# rcstick-f.net
KiCad netlist of a schematic drawn in EAGLE
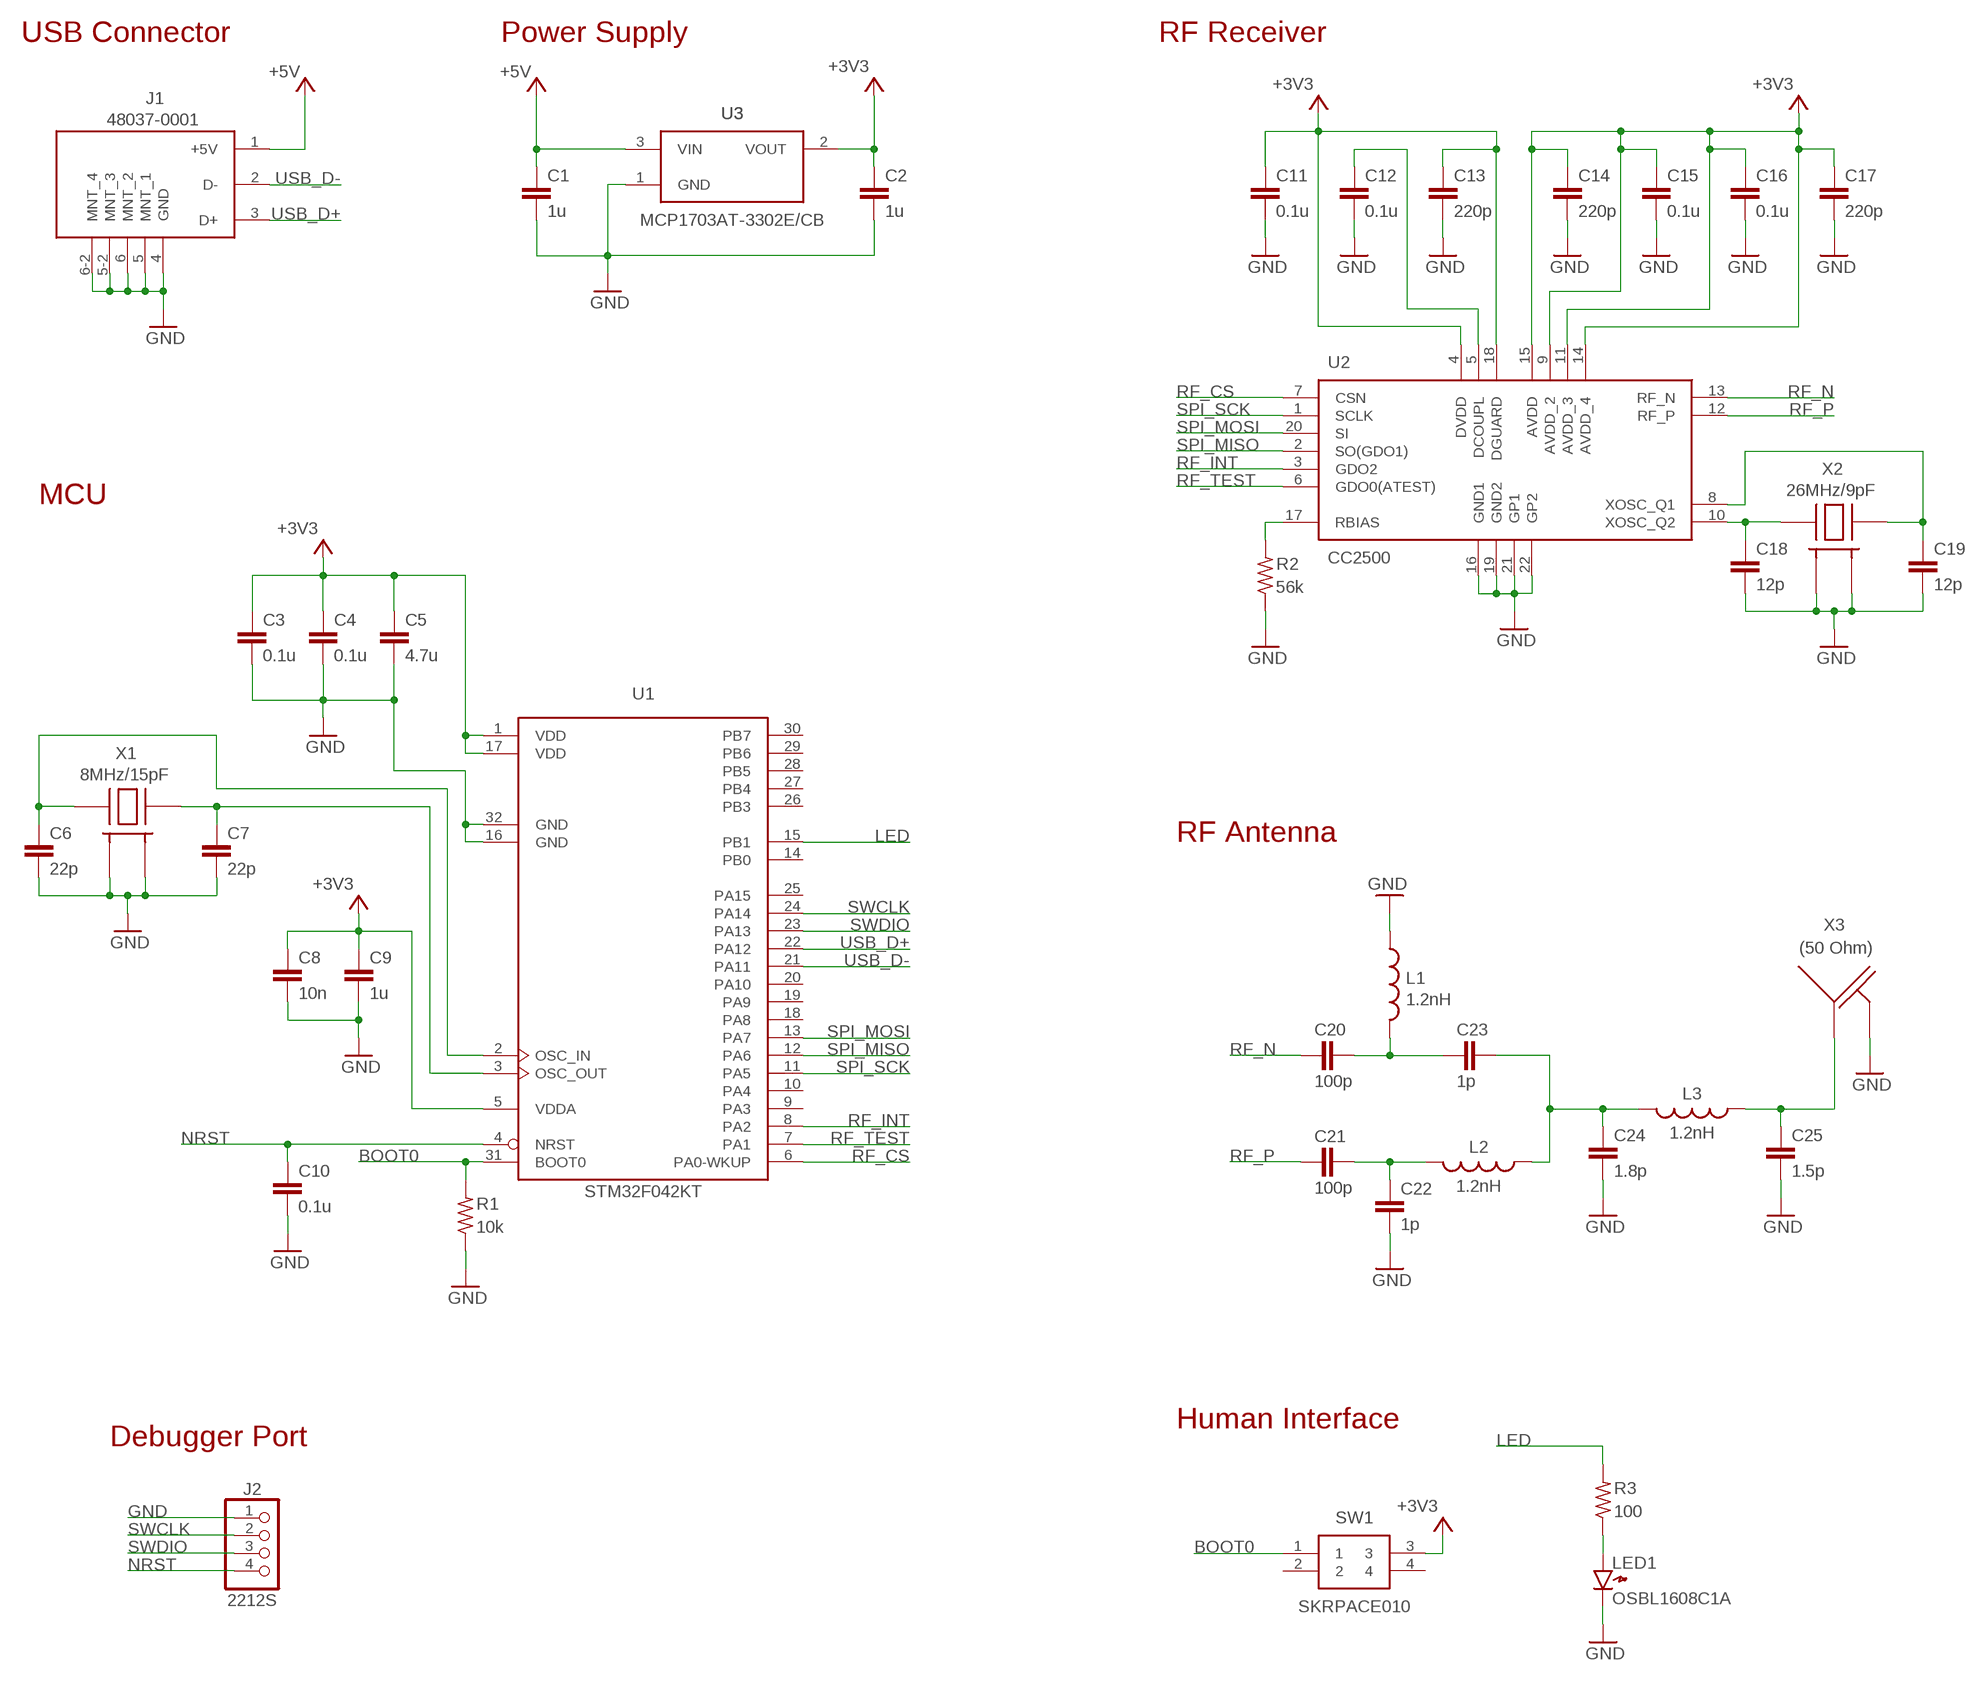
[diagram p0: schematic, sheet 1]

(export (version "E")
  (design (tool "Eeschema 10.0.6"))
  (components
    (comp (ref "C1")
      (value "1u")
      (footprint "eagle-import:RCL_C0402_HS")
      (libsource (lib "eagle-import") (part "RCL_C-EUC0402-HS"))
    )
    (comp (ref "C2")
      (value "1u")
      (footprint "eagle-import:RCL_C0402_HS")
      (libsource (lib "eagle-import") (part "RCL_C-EUC0402-HS"))
    )
    (comp (ref "C3")
      (value "0.1u")
      (footprint "eagle-import:RCL_C0402_HS")
      (libsource (lib "eagle-import") (part "RCL_C-EUC0402-HS"))
    )
    (comp (ref "C4")
      (value "0.1u")
      (footprint "eagle-import:RCL_C0402_HS")
      (libsource (lib "eagle-import") (part "RCL_C-EUC0402-HS"))
    )
    (comp (ref "C5")
      (value "4.7u")
      (footprint "eagle-import:RCL_C0402_HS")
      (libsource (lib "eagle-import") (part "RCL_C-EUC0402-HS"))
    )
    (comp (ref "C6")
      (value "22p")
      (footprint "eagle-import:RCL_C0402_HS")
      (libsource (lib "eagle-import") (part "RCL_C-EUC0402-HS"))
    )
    (comp (ref "C7")
      (value "22p")
      (footprint "eagle-import:RCL_C0402_HS")
      (libsource (lib "eagle-import") (part "RCL_C-EUC0402-HS"))
    )
    (comp (ref "C8")
      (value "10n")
      (footprint "eagle-import:RCL_C0402_HS")
      (libsource (lib "eagle-import") (part "RCL_C-EUC0402-HS"))
    )
    (comp (ref "C9")
      (value "1u")
      (footprint "eagle-import:RCL_C0402_HS")
      (libsource (lib "eagle-import") (part "RCL_C-EUC0402-HS"))
    )
    (comp (ref "C10")
      (value "0.1u")
      (footprint "eagle-import:RCL_C0402_HS")
      (libsource (lib "eagle-import") (part "RCL_C-EUC0402-HS"))
    )
    (comp (ref "C11")
      (value "0.1u")
      (footprint "eagle-import:RCL_C0402_HS")
      (libsource (lib "eagle-import") (part "RCL_C-EUC0402-HS"))
    )
    (comp (ref "C12")
      (value "0.1u")
      (footprint "eagle-import:RCL_C0402_HS")
      (libsource (lib "eagle-import") (part "RCL_C-EUC0402-HS"))
    )
    (comp (ref "C13")
      (value "220p")
      (footprint "eagle-import:RCL_C0402_HS")
      (libsource (lib "eagle-import") (part "RCL_C-EUC0402-HS"))
    )
    (comp (ref "C14")
      (value "220p")
      (footprint "eagle-import:RCL_C0402_HS")
      (libsource (lib "eagle-import") (part "RCL_C-EUC0402-HS"))
    )
    (comp (ref "C15")
      (value "0.1u")
      (footprint "eagle-import:RCL_C0402_HS")
      (libsource (lib "eagle-import") (part "RCL_C-EUC0402-HS"))
    )
    (comp (ref "C16")
      (value "0.1u")
      (footprint "eagle-import:RCL_C0402_HS")
      (libsource (lib "eagle-import") (part "RCL_C-EUC0402-HS"))
    )
    (comp (ref "C17")
      (value "220p")
      (footprint "eagle-import:RCL_C0402_HS")
      (libsource (lib "eagle-import") (part "RCL_C-EUC0402-HS"))
    )
    (comp (ref "C18")
      (value "12p")
      (footprint "eagle-import:RCL_C0402_HS")
      (libsource (lib "eagle-import") (part "RCL_C-EUC0402-HS"))
    )
    (comp (ref "C19")
      (value "12p")
      (footprint "eagle-import:RCL_C0402_HS")
      (libsource (lib "eagle-import") (part "RCL_C-EUC0402-HS"))
    )
    (comp (ref "C20")
      (value "100p")
      (footprint "eagle-import:RCL_C0402_HS")
      (libsource (lib "eagle-import") (part "RCL_C-EUC0402-HS"))
    )
    (comp (ref "C21")
      (value "100p")
      (footprint "eagle-import:RCL_C0402_HS")
      (libsource (lib "eagle-import") (part "RCL_C-EUC0402-HS"))
    )
    (comp (ref "C22")
      (value "1p")
      (footprint "eagle-import:RCL_C0402_HS")
      (libsource (lib "eagle-import") (part "RCL_C-EUC0402-HS"))
    )
    (comp (ref "C23")
      (value "1p")
      (footprint "eagle-import:RCL_C0402_HS")
      (libsource (lib "eagle-import") (part "RCL_C-EUC0402-HS"))
    )
    (comp (ref "C24")
      (value "1.8p")
      (footprint "eagle-import:RCL_C0402_HS")
      (libsource (lib "eagle-import") (part "RCL_C-EUC0402-HS"))
    )
    (comp (ref "C25")
      (value "1.5p")
      (footprint "eagle-import:RCL_C0402_HS")
      (libsource (lib "eagle-import") (part "RCL_C-EUC0402-HS"))
    )
    (comp (ref "J1")
      (value "MOLEX_48037-0001")
      (footprint "eagle-import:MOLEX_48037-0001_1")
      (libsource (lib "eagle-import") (part "MOLEX_48037-0001"))
    )
    (comp (ref "J2")
      (value "2212S")
      (footprint "eagle-import:CONNECTOR_STD-1X4")
      (libsource (lib "eagle-import") (part "CONNECTOR_STD-PINHD-1X4"))
    )
    (comp (ref "L1")
      (value "1.2nH")
      (footprint "eagle-import:RCL_L0402_HS")
      (libsource (lib "eagle-import") (part "RCL_L-USL0402-HS"))
    )
    (comp (ref "L2")
      (value "1.2nH")
      (footprint "eagle-import:RCL_L0402_HS")
      (libsource (lib "eagle-import") (part "RCL_L-USL0402-HS"))
    )
    (comp (ref "L3")
      (value "1.2nH")
      (footprint "eagle-import:RCL_L0402_HS")
      (libsource (lib "eagle-import") (part "RCL_L-USL0402-HS"))
    )
    (comp (ref "LED1")
      (value "OSBL1608C1A")
      (footprint "eagle-import:LED1608")
      (libsource (lib "eagle-import") (part "LED1608"))
    )
    (comp (ref "R1")
      (value "10k")
      (footprint "eagle-import:RCL_R0402_HS")
      (libsource (lib "eagle-import") (part "RCL_R-US_R0402-HS"))
    )
    (comp (ref "R2")
      (value "56k")
      (footprint "eagle-import:RCL_R0402_HS")
      (libsource (lib "eagle-import") (part "RCL_R-US_R0402-HS"))
    )
    (comp (ref "R3")
      (value "100")
      (footprint "eagle-import:RCL_R0402_HS")
      (libsource (lib "eagle-import") (part "RCL_R-US_R0402-HS"))
    )
    (comp (ref "SW1")
      (value "SKRPACE010")
      (footprint "eagle-import:SMT(4.2X3.2)")
      (libsource (lib "eagle-import") (part "SKRPACE010"))
    )
    (comp (ref "U1")
      (value "STM32F042KT")
      (footprint "eagle-import:LQFP32-M")
      (libsource (lib "eagle-import") (part "STM32F042KT"))
    )
    (comp (ref "U2")
      (value "CC2500")
      (footprint "eagle-import:CC2500-RTY1_CC2500-HS")
      (libsource (lib "eagle-import") (part "CC2500-HS"))
    )
    (comp (ref "U3")
      (value "MCP1703AT-3302E/CB")
      (footprint "eagle-import:SOT23")
      (libsource (lib "eagle-import") (part "LDO-REGULATOR"))
    )
    (comp (ref "X1")
      (value "8MHz/15pF")
      (footprint "eagle-import:CRYSTAL3225-HS")
      (libsource (lib "eagle-import") (part "CRYSTAL3225HS"))
    )
    (comp (ref "X2")
      (value "26MHz/9pF")
      (footprint "eagle-import:CRYSTAL3225-HS")
      (libsource (lib "eagle-import") (part "CRYSTAL3225HS"))
    )
    (comp (ref "X3")
      (value "(50 Ohm)")
      (footprint "eagle-import:2.4GHZ-INVERTED-F-LARGE-FLIP")
      (libsource (lib "eagle-import") (part "2.4GHZ-INVERED-FLARGE-FLIP"))
    )
  )
  (nets
    (net (code "1") (name "+3V3") (class "Default")
      (node (ref "C11") (pin "1") (pinfunction "1_1") (pintype "passive"))
      (node (ref "C13") (pin "1") (pinfunction "1_1") (pintype "passive"))
      (node (ref "C14") (pin "1") (pinfunction "1_1") (pintype "passive"))
      (node (ref "C15") (pin "1") (pinfunction "1_1") (pintype "passive"))
      (node (ref "C16") (pin "1") (pinfunction "1_1") (pintype "passive"))
      (node (ref "C17") (pin "1") (pinfunction "1_1") (pintype "passive"))
      (node (ref "C2") (pin "1") (pinfunction "1_1") (pintype "passive"))
      (node (ref "C3") (pin "1") (pinfunction "1_1") (pintype "passive"))
      (node (ref "C4") (pin "1") (pinfunction "1_1") (pintype "passive"))
      (node (ref "C5") (pin "1") (pinfunction "1_1") (pintype "passive"))
      (node (ref "C8") (pin "1") (pinfunction "1_1") (pintype "passive"))
      (node (ref "C9") (pin "1") (pinfunction "1_1") (pintype "passive"))
      (node (ref "SW1") (pin "3") (pinfunction "3_3") (pintype "bidirectional"))
      (node (ref "U1") (pin "1") (pinfunction "VDD_1") (pintype "power_in"))
      (node (ref "U1") (pin "17") (pinfunction "VDD_17") (pintype "power_in"))
      (node (ref "U1") (pin "5") (pinfunction "VDDA_5") (pintype "power_in"))
      (node (ref "U2") (pin "11") (pinfunction "AVDD_3_11") (pintype "bidirectional"))
      (node (ref "U2") (pin "14") (pinfunction "AVDD_4_14") (pintype "bidirectional"))
      (node (ref "U2") (pin "15") (pinfunction "AVDD_15") (pintype "bidirectional"))
      (node (ref "U2") (pin "18") (pinfunction "DGUARD_18") (pintype "bidirectional"))
      (node (ref "U2") (pin "4") (pinfunction "DVDD_4") (pintype "bidirectional"))
      (node (ref "U2") (pin "9") (pinfunction "AVDD_2_9") (pintype "bidirectional"))
      (node (ref "U3") (pin "2") (pinfunction "VOUT_2") (pintype "bidirectional"))
    )
    (net (code "2") (name "+5V") (class "Default")
      (node (ref "C1") (pin "1") (pinfunction "1_1") (pintype "passive"))
      (node (ref "J1") (pin "1") (pinfunction "+5V_1") (pintype "bidirectional"))
      (node (ref "U3") (pin "3") (pinfunction "VIN_3") (pintype "bidirectional"))
    )
    (net (code "3") (name "/BOOT0") (class "Default")
      (node (ref "R1") (pin "2") (pinfunction "2_2") (pintype "passive"))
      (node (ref "SW1") (pin "1") (pinfunction "1_1") (pintype "bidirectional"))
      (node (ref "U1") (pin "31") (pinfunction "BOOT0_31") (pintype "input"))
    )
    (net (code "4") (name "/LED") (class "Default")
      (node (ref "R3") (pin "2") (pinfunction "2_2") (pintype "passive"))
      (node (ref "U1") (pin "15") (pinfunction "PB1_15") (pintype "bidirectional"))
    )
    (net (code "5") (name "/NRST") (class "Default")
      (node (ref "C10") (pin "1") (pinfunction "1_1") (pintype "passive"))
      (node (ref "J2") (pin "4") (pinfunction "4_4") (pintype "passive"))
      (node (ref "U1") (pin "4") (pinfunction "NRST_4") (pintype "bidirectional"))
    )
    (net (code "6") (name "/RF_CS") (class "Default")
      (node (ref "U1") (pin "6") (pinfunction "PA0-WKUP_6") (pintype "bidirectional"))
      (node (ref "U2") (pin "7") (pinfunction "CSN_7") (pintype "bidirectional"))
    )
    (net (code "7") (name "/RF_INT") (class "Default")
      (node (ref "U1") (pin "8") (pinfunction "PA2_8") (pintype "bidirectional"))
      (node (ref "U2") (pin "3") (pinfunction "GDO2_3") (pintype "bidirectional"))
    )
    (net (code "8") (name "/RF_N") (class "Default")
      (node (ref "C20") (pin "1") (pinfunction "1_1") (pintype "passive"))
      (node (ref "U2") (pin "13") (pinfunction "RF_N_13") (pintype "bidirectional"))
    )
    (net (code "9") (name "/RF_P") (class "Default")
      (node (ref "C21") (pin "1") (pinfunction "1_1") (pintype "passive"))
      (node (ref "U2") (pin "12") (pinfunction "RF_P_12") (pintype "bidirectional"))
    )
    (net (code "10") (name "/RF_TEST") (class "Default")
      (node (ref "U1") (pin "7") (pinfunction "PA1_7") (pintype "bidirectional"))
      (node (ref "U2") (pin "6") (pinfunction "GDO0(ATEST)_6") (pintype "bidirectional"))
    )
    (net (code "11") (name "/SPI_MISO") (class "Default")
      (node (ref "U1") (pin "12") (pinfunction "PA6_12") (pintype "bidirectional"))
      (node (ref "U2") (pin "2") (pinfunction "SO(GDO1)_2") (pintype "bidirectional"))
    )
    (net (code "12") (name "/SPI_MOSI") (class "Default")
      (node (ref "U1") (pin "13") (pinfunction "PA7_13") (pintype "bidirectional"))
      (node (ref "U2") (pin "20") (pinfunction "SI_20") (pintype "bidirectional"))
    )
    (net (code "13") (name "/SPI_SCK") (class "Default")
      (node (ref "U1") (pin "11") (pinfunction "PA5_11") (pintype "bidirectional"))
      (node (ref "U2") (pin "1") (pinfunction "SCLK_1") (pintype "bidirectional"))
    )
    (net (code "14") (name "/SWCLK") (class "Default")
      (node (ref "J2") (pin "2") (pinfunction "2_2") (pintype "passive"))
      (node (ref "U1") (pin "24") (pinfunction "PA14_24") (pintype "bidirectional"))
    )
    (net (code "15") (name "/SWDIO") (class "Default")
      (node (ref "J2") (pin "3") (pinfunction "3_3") (pintype "passive"))
      (node (ref "U1") (pin "23") (pinfunction "PA13_23") (pintype "bidirectional"))
    )
    (net (code "16") (name "/USB_D+") (class "Default")
      (node (ref "J1") (pin "3") (pinfunction "D+_3") (pintype "bidirectional"))
      (node (ref "U1") (pin "22") (pinfunction "PA12_22") (pintype "bidirectional"))
    )
    (net (code "17") (name "/USB_D-") (class "Default")
      (node (ref "J1") (pin "2") (pinfunction "D-_2") (pintype "bidirectional"))
      (node (ref "U1") (pin "21") (pinfunction "PA11_21") (pintype "bidirectional"))
    )
    (net (code "18") (name "GND") (class "Default")
      (node (ref "C1") (pin "2") (pinfunction "2_2") (pintype "passive"))
      (node (ref "C10") (pin "2") (pinfunction "2_2") (pintype "passive"))
      (node (ref "C11") (pin "2") (pinfunction "2_2") (pintype "passive"))
      (node (ref "C12") (pin "2") (pinfunction "2_2") (pintype "passive"))
      (node (ref "C13") (pin "2") (pinfunction "2_2") (pintype "passive"))
      (node (ref "C14") (pin "2") (pinfunction "2_2") (pintype "passive"))
      (node (ref "C15") (pin "2") (pinfunction "2_2") (pintype "passive"))
      (node (ref "C16") (pin "2") (pinfunction "2_2") (pintype "passive"))
      (node (ref "C17") (pin "2") (pinfunction "2_2") (pintype "passive"))
      (node (ref "C18") (pin "2") (pinfunction "2_2") (pintype "passive"))
      (node (ref "C19") (pin "2") (pinfunction "2_2") (pintype "passive"))
      (node (ref "C2") (pin "2") (pinfunction "2_2") (pintype "passive"))
      (node (ref "C22") (pin "2") (pinfunction "2_2") (pintype "passive"))
      (node (ref "C24") (pin "2") (pinfunction "2_2") (pintype "passive"))
      (node (ref "C25") (pin "2") (pinfunction "2_2") (pintype "passive"))
      (node (ref "C3") (pin "2") (pinfunction "2_2") (pintype "passive"))
      (node (ref "C4") (pin "2") (pinfunction "2_2") (pintype "passive"))
      (node (ref "C5") (pin "2") (pinfunction "2_2") (pintype "passive"))
      (node (ref "C6") (pin "2") (pinfunction "2_2") (pintype "passive"))
      (node (ref "C7") (pin "2") (pinfunction "2_2") (pintype "passive"))
      (node (ref "C8") (pin "2") (pinfunction "2_2") (pintype "passive"))
      (node (ref "C9") (pin "2") (pinfunction "2_2") (pintype "passive"))
      (node (ref "J1") (pin "4") (pinfunction "GND_4") (pintype "bidirectional"))
      (node (ref "J1") (pin "5") (pinfunction "MNT_1_5") (pintype "bidirectional"))
      (node (ref "J1") (pin "5-2") (pinfunction "MNT_3_5-2") (pintype "bidirectional"))
      (node (ref "J1") (pin "6") (pinfunction "MNT_2_6") (pintype "bidirectional"))
      (node (ref "J1") (pin "6-2") (pinfunction "MNT_4_6-2") (pintype "bidirectional"))
      (node (ref "J2") (pin "1") (pinfunction "1_1") (pintype "passive"))
      (node (ref "L1") (pin "1") (pinfunction "1_1") (pintype "passive"))
      (node (ref "LED1") (pin "K") (pinfunction "K_K") (pintype "passive"))
      (node (ref "R1") (pin "1") (pinfunction "1_1") (pintype "passive"))
      (node (ref "R2") (pin "1") (pinfunction "1_1") (pintype "passive"))
      (node (ref "U1") (pin "16") (pinfunction "GND_16") (pintype "power_in"))
      (node (ref "U1") (pin "32") (pinfunction "GND_32") (pintype "power_in"))
      (node (ref "U2") (pin "16") (pinfunction "GND1_16") (pintype "bidirectional"))
      (node (ref "U2") (pin "19") (pinfunction "GND2_19") (pintype "bidirectional"))
      (node (ref "U2") (pin "21") (pinfunction "GP1_21") (pintype "bidirectional"))
      (node (ref "U2") (pin "22") (pinfunction "GP2_22") (pintype "bidirectional"))
      (node (ref "U3") (pin "1") (pinfunction "GND_1") (pintype "bidirectional"))
      (node (ref "X1") (pin "2") (pinfunction "GND_1_2") (pintype "bidirectional"))
      (node (ref "X1") (pin "4") (pinfunction "GND_2_4") (pintype "bidirectional"))
      (node (ref "X2") (pin "2") (pinfunction "GND_1_2") (pintype "bidirectional"))
      (node (ref "X2") (pin "4") (pinfunction "GND_2_4") (pintype "bidirectional"))
      (node (ref "X3") (pin "2") (pinfunction "GND_2") (pintype "bidirectional"))
    )
    (net (code "19") (name "Net-(C20-Pad2)") (class "Default")
      (node (ref "C20") (pin "2") (pinfunction "2_2") (pintype "passive"))
      (node (ref "C23") (pin "1") (pinfunction "1_1") (pintype "passive"))
      (node (ref "L1") (pin "2") (pinfunction "2_2") (pintype "passive"))
    )
    (net (code "20") (name "Net-(C21-Pad2)") (class "Default")
      (node (ref "C21") (pin "2") (pinfunction "2_2") (pintype "passive"))
      (node (ref "C22") (pin "1") (pinfunction "1_1") (pintype "passive"))
      (node (ref "L2") (pin "2") (pinfunction "2_2") (pintype "passive"))
    )
    (net (code "21") (name "Net-(C23-Pad2)") (class "Default")
      (node (ref "C23") (pin "2") (pinfunction "2_2") (pintype "passive"))
      (node (ref "C24") (pin "1") (pinfunction "1_1") (pintype "passive"))
      (node (ref "L2") (pin "1") (pinfunction "1_1") (pintype "passive"))
      (node (ref "L3") (pin "2") (pinfunction "2_2") (pintype "passive"))
    )
    (net (code "22") (name "Net-(LED1-PadA)") (class "Default")
      (node (ref "LED1") (pin "A") (pinfunction "A_A") (pintype "passive"))
      (node (ref "R3") (pin "1") (pinfunction "1_1") (pintype "passive"))
    )
    (net (code "23") (name "Net-(U1-OSC_IN)") (class "Default")
      (node (ref "C6") (pin "1") (pinfunction "1_1") (pintype "passive"))
      (node (ref "U1") (pin "2") (pinfunction "OSC_IN_2") (pintype "bidirectional"))
      (node (ref "X1") (pin "1") (pinfunction "HOT_1_1") (pintype "bidirectional"))
    )
    (net (code "24") (name "Net-(U1-OSC_OUT)") (class "Default")
      (node (ref "C7") (pin "1") (pinfunction "1_1") (pintype "passive"))
      (node (ref "U1") (pin "3") (pinfunction "OSC_OUT_3") (pintype "bidirectional"))
      (node (ref "X1") (pin "3") (pinfunction "HOT_2_3") (pintype "bidirectional"))
    )
    (net (code "25") (name "Net-(U2-DCOUPL)") (class "Default")
      (node (ref "C12") (pin "1") (pinfunction "1_1") (pintype "passive"))
      (node (ref "U2") (pin "5") (pinfunction "DCOUPL_5") (pintype "bidirectional"))
    )
    (net (code "26") (name "Net-(U2-RBIAS)") (class "Default")
      (node (ref "R2") (pin "2") (pinfunction "2_2") (pintype "passive"))
      (node (ref "U2") (pin "17") (pinfunction "RBIAS_17") (pintype "bidirectional"))
    )
    (net (code "27") (name "Net-(U2-XOSC_Q1)") (class "Default")
      (node (ref "C19") (pin "1") (pinfunction "1_1") (pintype "passive"))
      (node (ref "U2") (pin "8") (pinfunction "XOSC_Q1_8") (pintype "bidirectional"))
      (node (ref "X2") (pin "3") (pinfunction "HOT_2_3") (pintype "bidirectional"))
    )
    (net (code "28") (name "Net-(U2-XOSC_Q2)") (class "Default")
      (node (ref "C18") (pin "1") (pinfunction "1_1") (pintype "passive"))
      (node (ref "U2") (pin "10") (pinfunction "XOSC_Q2_10") (pintype "bidirectional"))
      (node (ref "X2") (pin "1") (pinfunction "HOT_1_1") (pintype "bidirectional"))
    )
    (net (code "29") (name "Net-(X3-ANT)") (class "Default")
      (node (ref "C25") (pin "1") (pinfunction "1_1") (pintype "passive"))
      (node (ref "L3") (pin "1") (pinfunction "1_1") (pintype "passive"))
      (node (ref "X3") (pin "1") (pinfunction "ANT_1") (pintype "bidirectional"))
    )
    (net (code "30") (name "unconnected-(SW1-Pad2)") (class "Default")
      (node (ref "SW1") (pin "2") (pinfunction "2_2") (pintype "bidirectional"))
    )
    (net (code "31") (name "unconnected-(SW1-Pad4)") (class "Default")
      (node (ref "SW1") (pin "4") (pinfunction "4_4") (pintype "bidirectional"))
    )
    (net (code "32") (name "unconnected-(U1-PA3-Pad9)") (class "Default")
      (node (ref "U1") (pin "9") (pinfunction "PA3_9") (pintype "bidirectional"))
    )
    (net (code "33") (name "unconnected-(U1-PA4-Pad10)") (class "Default")
      (node (ref "U1") (pin "10") (pinfunction "PA4_10") (pintype "bidirectional"))
    )
    (net (code "34") (name "unconnected-(U1-PA8-Pad18)") (class "Default")
      (node (ref "U1") (pin "18") (pinfunction "PA8_18") (pintype "bidirectional"))
    )
    (net (code "35") (name "unconnected-(U1-PA9-Pad19)") (class "Default")
      (node (ref "U1") (pin "19") (pinfunction "PA9_19") (pintype "bidirectional"))
    )
    (net (code "36") (name "unconnected-(U1-PA10-Pad20)") (class "Default")
      (node (ref "U1") (pin "20") (pinfunction "PA10_20") (pintype "bidirectional"))
    )
    (net (code "37") (name "unconnected-(U1-PA15-Pad25)") (class "Default")
      (node (ref "U1") (pin "25") (pinfunction "PA15_25") (pintype "bidirectional"))
    )
    (net (code "38") (name "unconnected-(U1-PB0-Pad14)") (class "Default")
      (node (ref "U1") (pin "14") (pinfunction "PB0_14") (pintype "bidirectional"))
    )
    (net (code "39") (name "unconnected-(U1-PB3-Pad26)") (class "Default")
      (node (ref "U1") (pin "26") (pinfunction "PB3_26") (pintype "bidirectional"))
    )
    (net (code "40") (name "unconnected-(U1-PB4-Pad27)") (class "Default")
      (node (ref "U1") (pin "27") (pinfunction "PB4_27") (pintype "bidirectional"))
    )
    (net (code "41") (name "unconnected-(U1-PB5-Pad28)") (class "Default")
      (node (ref "U1") (pin "28") (pinfunction "PB5_28") (pintype "bidirectional"))
    )
    (net (code "42") (name "unconnected-(U1-PB6-Pad29)") (class "Default")
      (node (ref "U1") (pin "29") (pinfunction "PB6_29") (pintype "bidirectional"))
    )
    (net (code "43") (name "unconnected-(U1-PB7-Pad30)") (class "Default")
      (node (ref "U1") (pin "30") (pinfunction "PB7_30") (pintype "bidirectional"))
    )
  )
)
